# CanSat_ADCS.net
KiCad netlist of a schematic drawn in Altium Designer
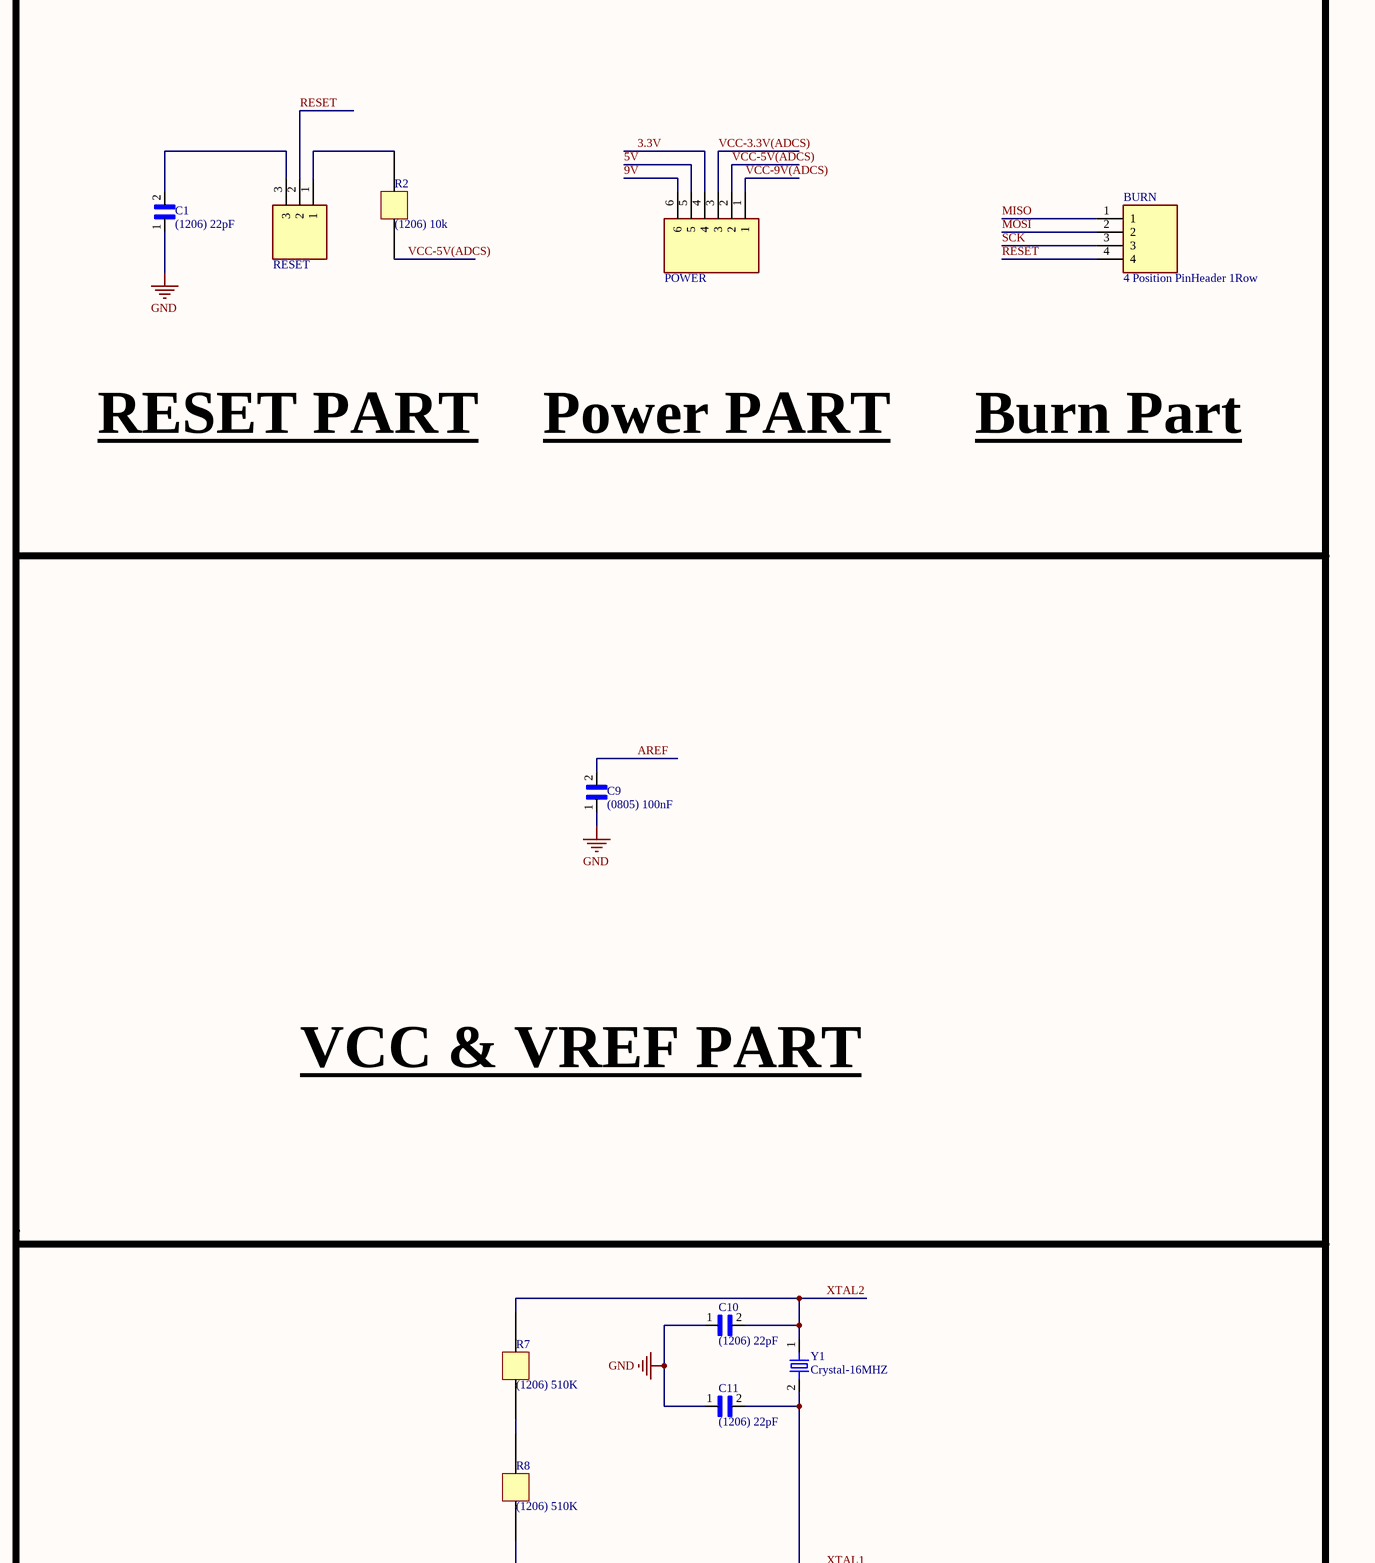
[diagram p0: CanSat ADCS.SchDoc, top left]
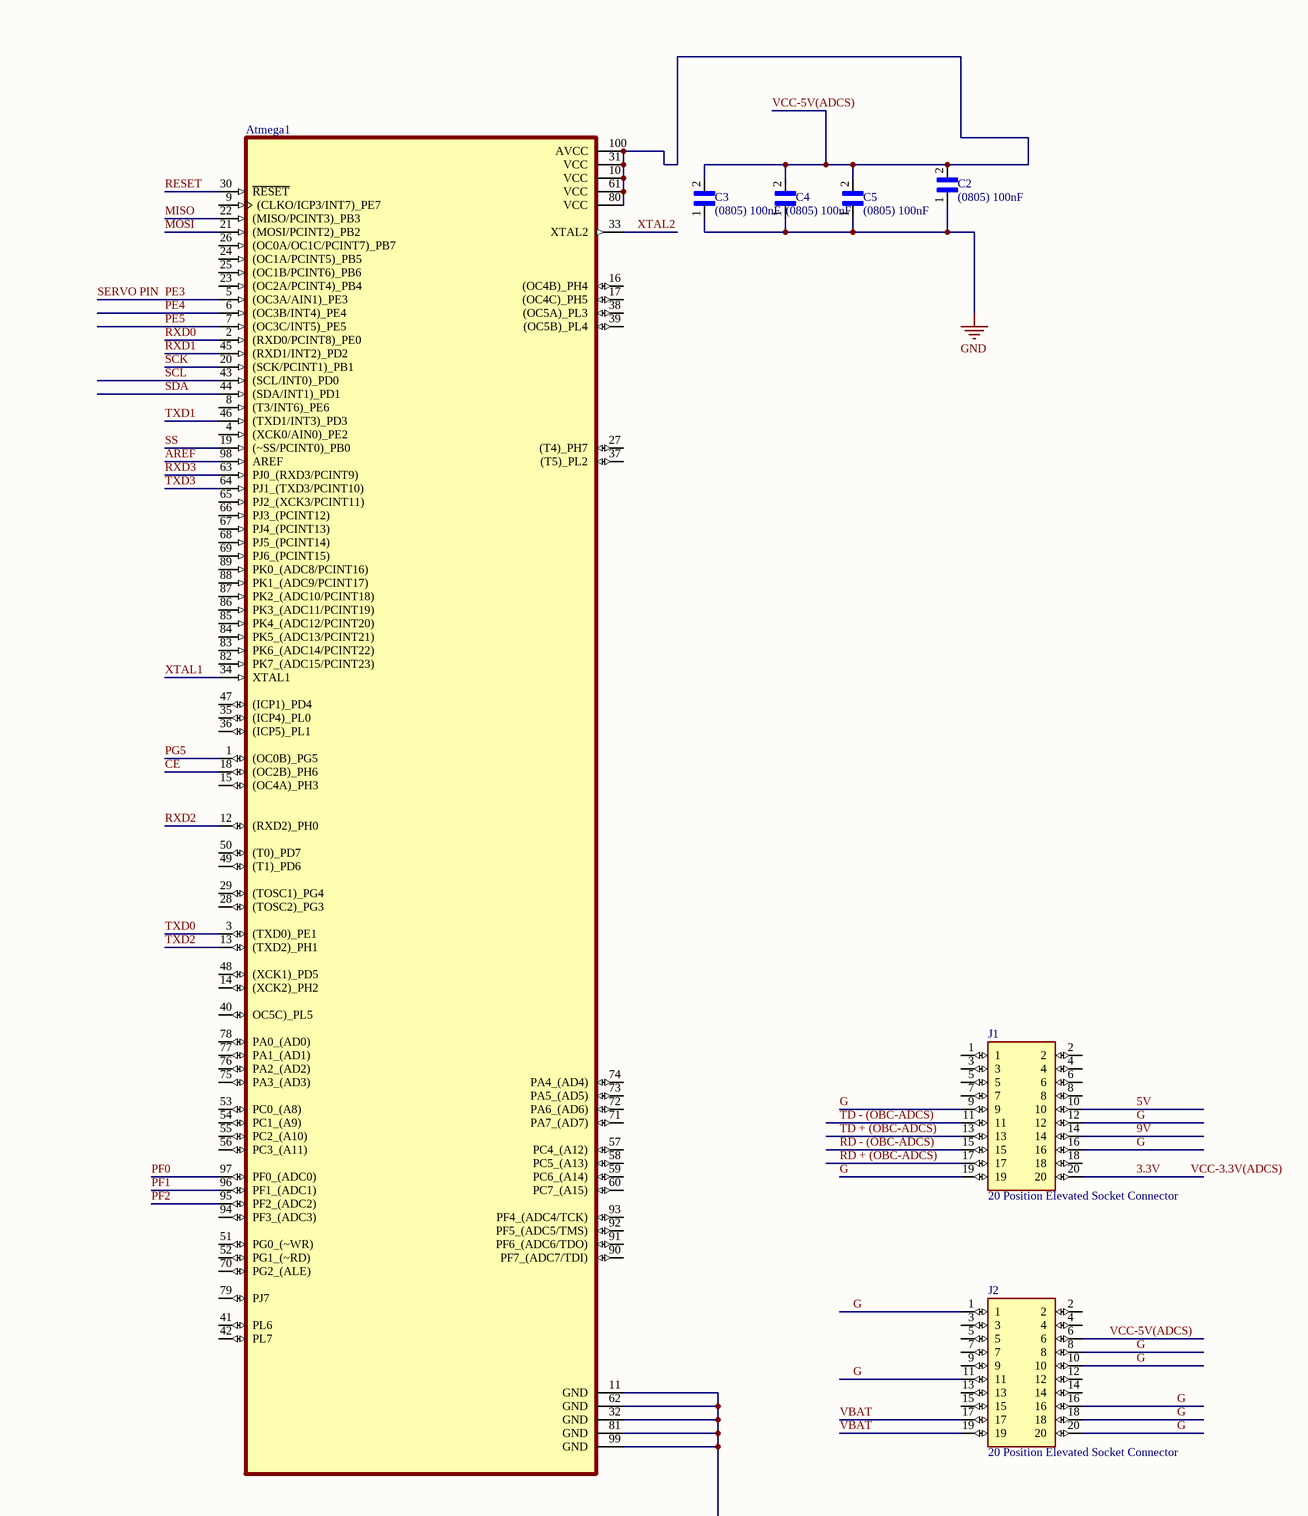
[diagram p1: CanSat ADCS.SchDoc, top middle]
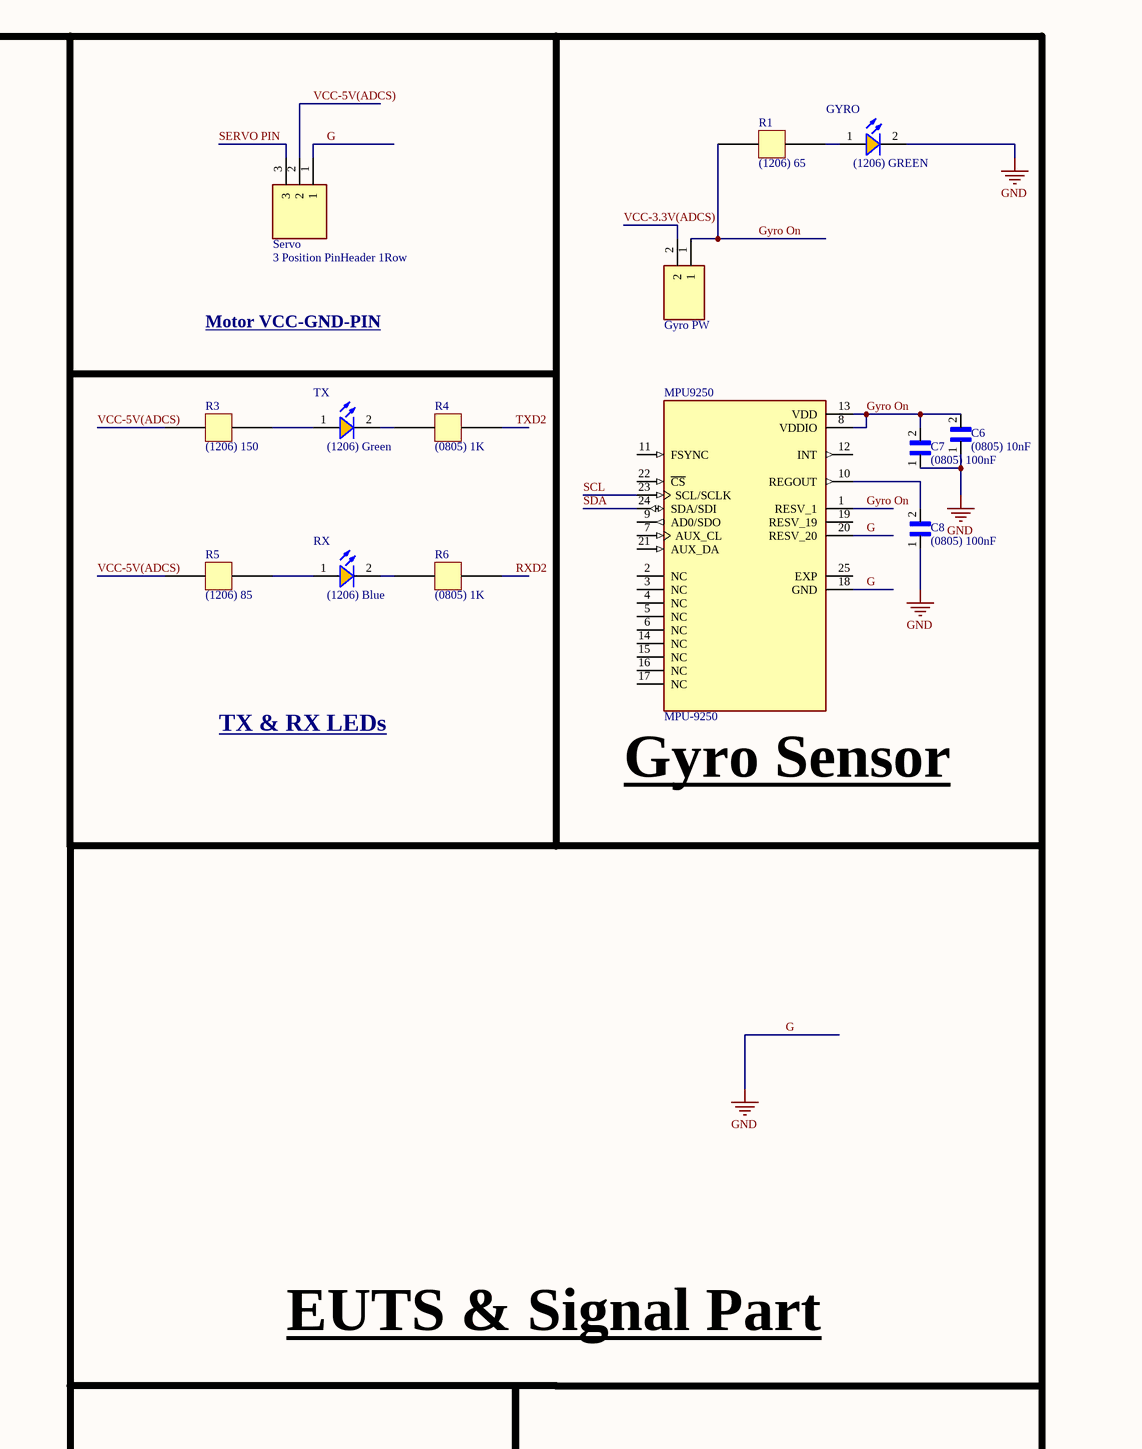
[diagram p2: CanSat ADCS.SchDoc, top right]
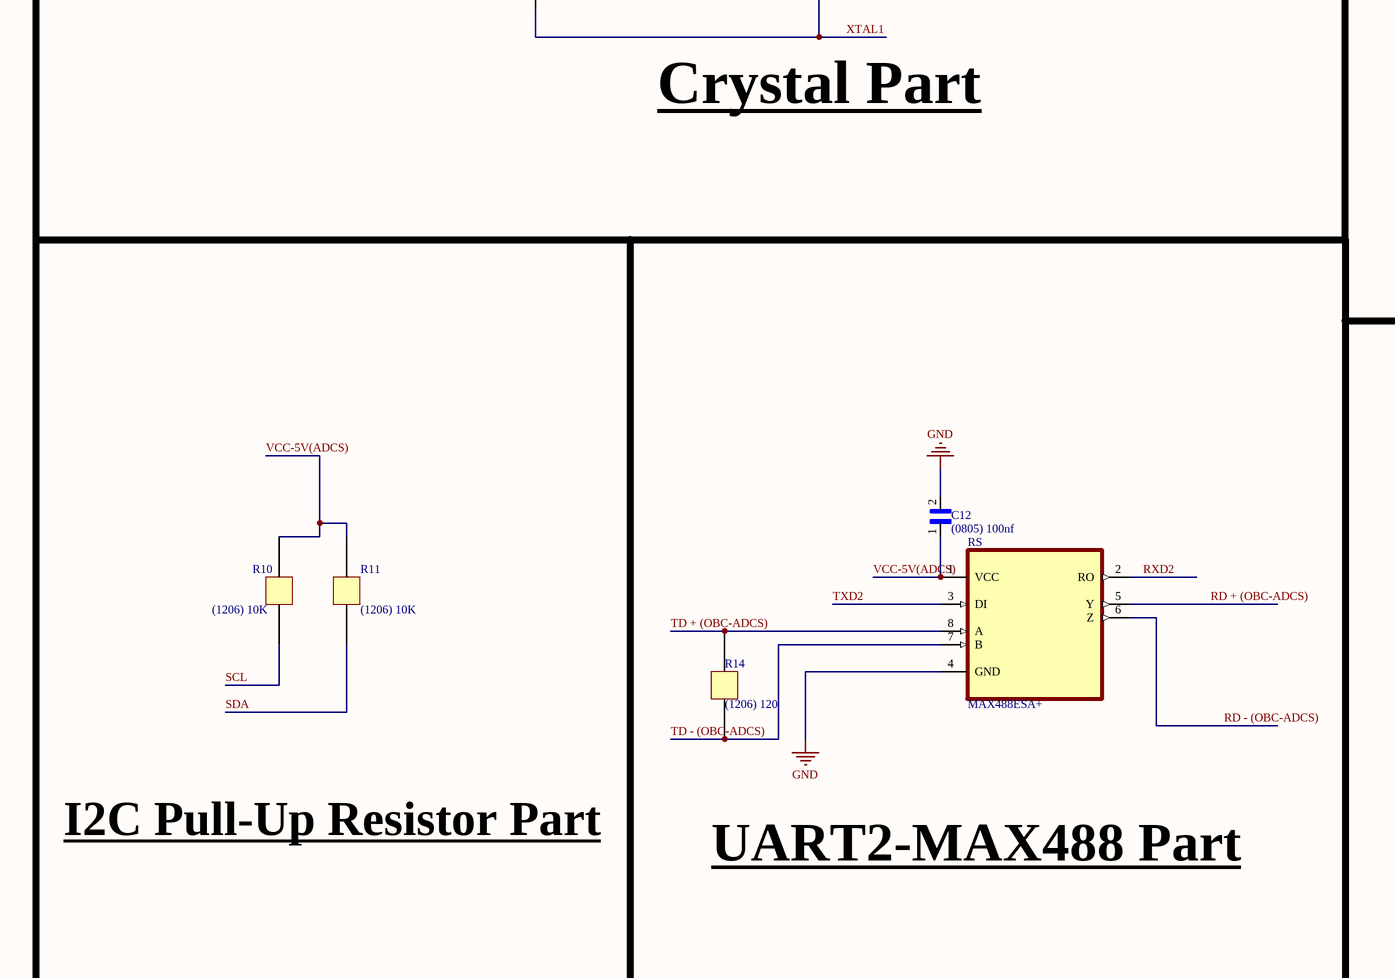
[diagram p3: CanSat ADCS.SchDoc, bottom left]
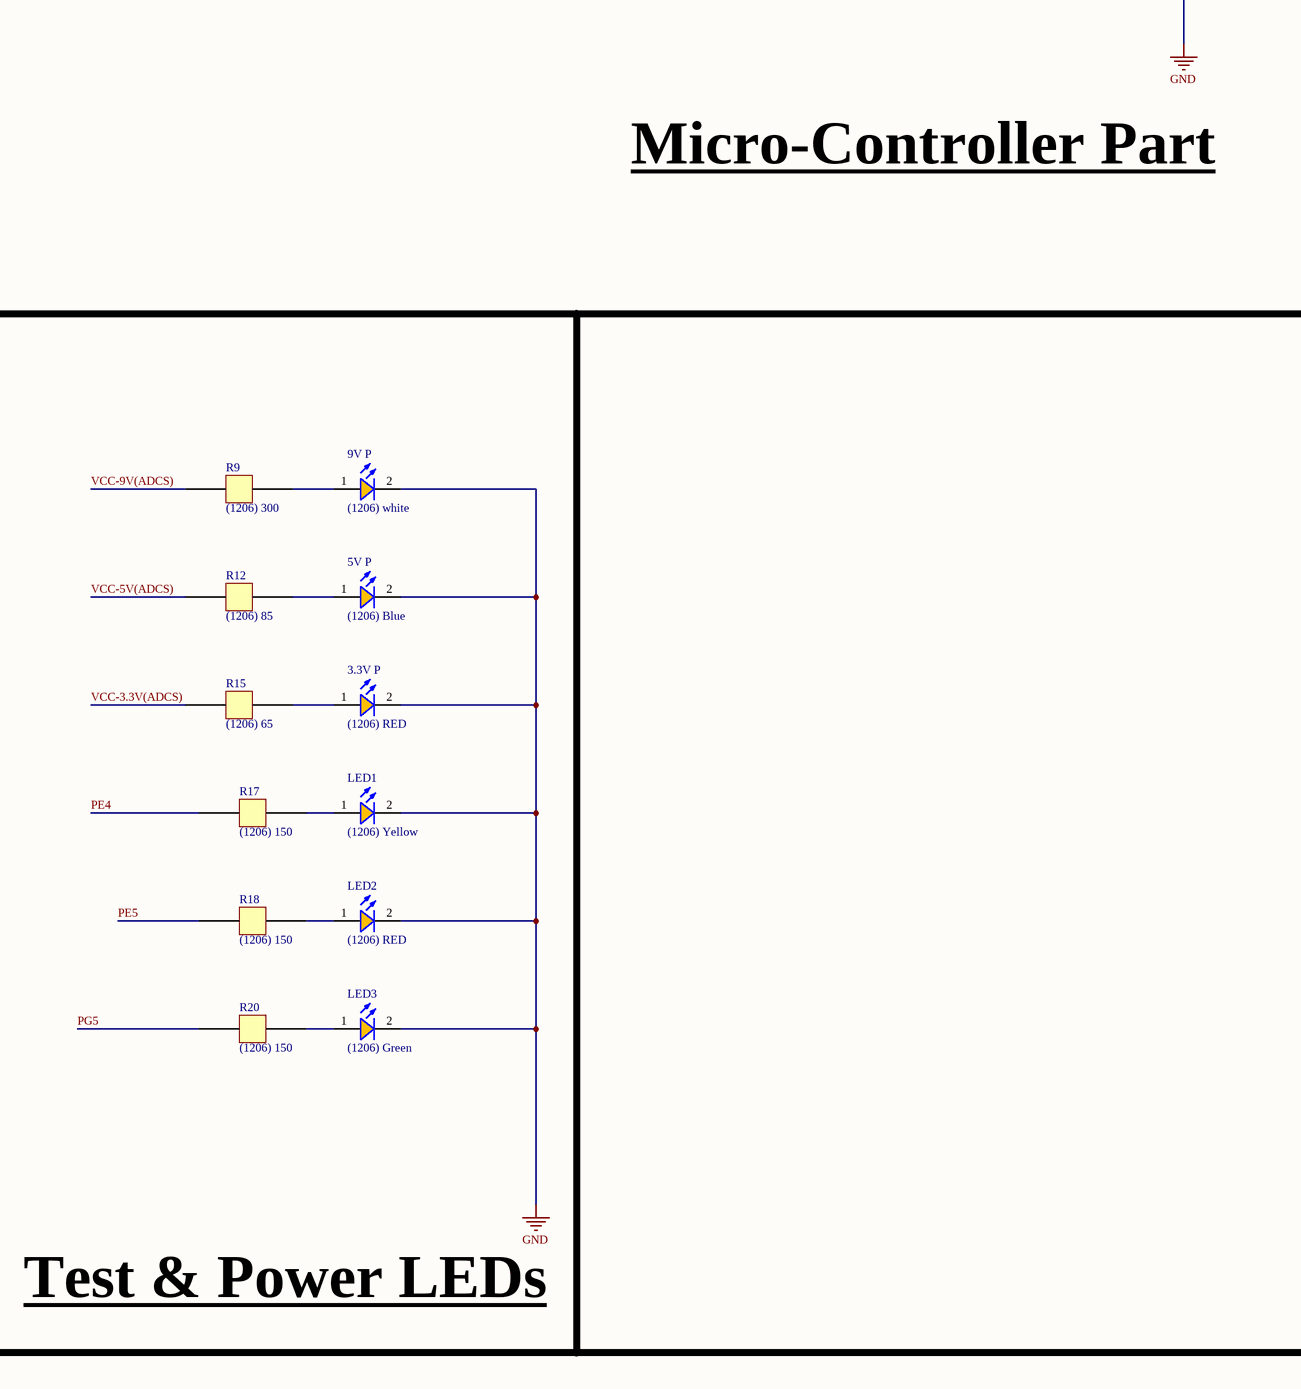
[diagram p4: CanSat ADCS.SchDoc, bottom middle]
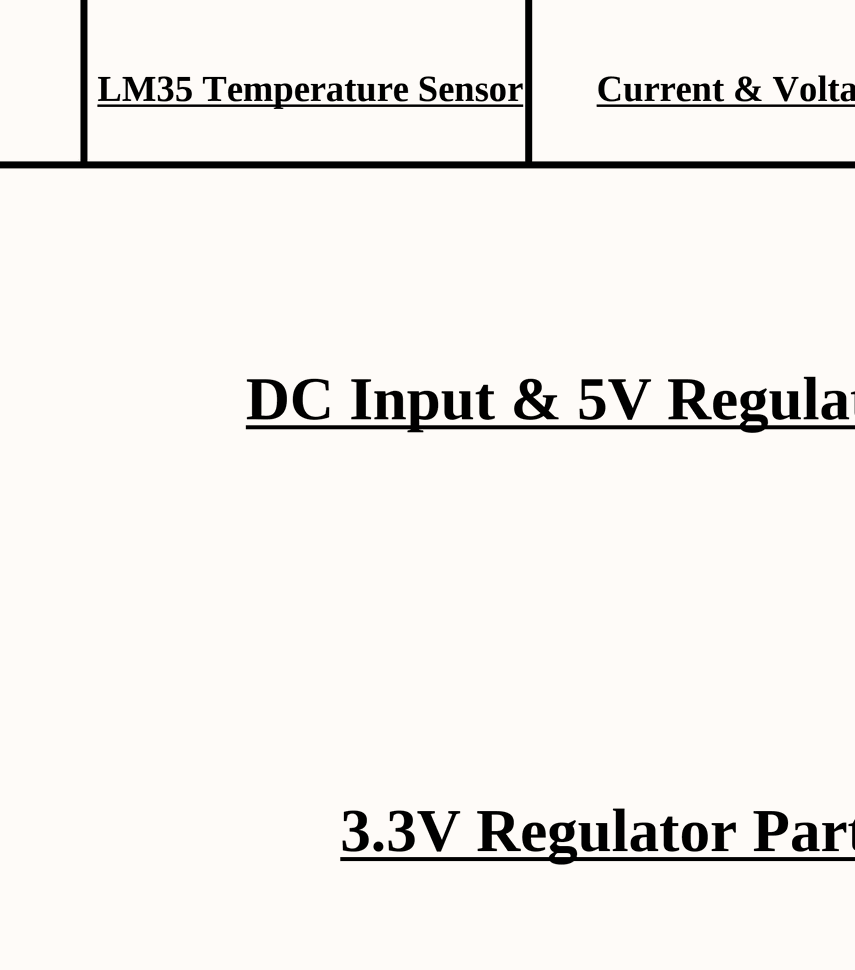
[diagram p5: CanSat ADCS.SchDoc, bottom right]

(export (version "E")
  (design (tool "Eeschema 10.0.6"))
  (components
    (comp (ref "3.3V P")
      (value "(1206) RED")
      (footprint "RESC3015X65-01")
      (description "LED SMD 1206 High Quality Forward Voltage: 3.2 V\r\nBrightness: 700 mcd")
      (fields
        (field (name "MANUFACTURER") "Wurth Elektronik")
        (field (name "MANUFACTURER PART NUMBER") "150060AS75003")
      )
      (libsource (lib "NewLib") (part "LED 1206"))
    )
    (comp (ref "5V P")
      (value "(1206) Blue")
      (footprint "RESC3015X65-01")
      (description "LED SMD 1206 High Quality Forward Voltage: 3.2 V\r\nBrightness: 700 mcd")
      (fields
        (field (name "MANUFACTURER") "Wurth Elektronik")
        (field (name "MANUFACTURER PART NUMBER") "150060AS75003")
      )
      (libsource (lib "NewLib") (part "LED 1206"))
    )
    (comp (ref "9V P")
      (value "(1206) white")
      (footprint "RESC3015X65-01")
      (description "LED SMD 1206 High Quality Forward Voltage: 3.2 V\r\nBrightness: 700 mcd")
      (fields
        (field (name "MANUFACTURER") "Wurth Elektronik")
        (field (name "MANUFACTURER PART NUMBER") "150060AS75003")
      )
      (libsource (lib "NewLib") (part "LED 1206"))
    )
    (comp (ref "Atmega1")
      (value "~")
      (footprint "QFP50P1600X1600X120-100N")
      (fields (field (name "MP") "ATMEGA2560-16AU"))
      (libsource (lib "NewLib") (part "ATMEGA2560-16AU"))
    )
    (comp (ref "BURN")
      (value "4 Position PinHeader 1Row")
      (footprint "TE_3-644456-4")
      (description "Conn Unshrouded Header HDR 4 POS 2.54mm Solder ST Thru-Hole Bag/Box")
      (fields (field (name "MP") "3-644456-4") (field (name "MF") "TE Connectivity"))
      (libsource (lib "NewLib") (part "4 Position PinHeader 1Row"))
    )
    (comp (ref "C1")
      (value "(1206) 22pF")
      (footprint "CAPC3216X125N0")
      (description "UMF316B7103KFHT/1206 Capacitor")
      (fields (field (name "MP") "UMF316B7103KFHT"))
      (libsource (lib "") (part "Capacitor 1206_1"))
    )
    (comp (ref "C2")
      (value "(0805) 100nF")
      (footprint "CAPC2012X95N-0")
      (description "UMK212SD103KD-T/CAP CER 10000PF 50V 0805")
      (fields (field (name "MP") "UMK212SD103KD-T"))
      (libsource (lib "NewLib") (part "Capacitor 0805"))
    )
    (comp (ref "C3")
      (value "(0805) 100nF")
      (footprint "CAPC2012X95N-0")
      (description "UMK212SD103KD-T/CAP CER 10000PF 50V 0805")
      (fields (field (name "MP") "UMK212SD103KD-T"))
      (libsource (lib "NewLib") (part "Capacitor 0805"))
    )
    (comp (ref "C4")
      (value "(0805) 100nF")
      (footprint "CAPC2012X95N-0")
      (description "UMK212SD103KD-T/CAP CER 10000PF 50V 0805")
      (fields (field (name "MP") "UMK212SD103KD-T"))
      (libsource (lib "NewLib") (part "Capacitor 0805"))
    )
    (comp (ref "C5")
      (value "(0805) 100nF")
      (footprint "CAPC2012X95N-0")
      (description "UMK212SD103KD-T/CAP CER 10000PF 50V 0805")
      (fields (field (name "MP") "UMK212SD103KD-T"))
      (libsource (lib "NewLib") (part "Capacitor 0805"))
    )
    (comp (ref "C6")
      (value "(0805) 10nF")
      (footprint "CAPC2012X95N-0")
      (description "UMK212SD103KD-T/CAP CER 10000PF 50V 0805")
      (fields (field (name "MP") "UMK212SD103KD-T"))
      (libsource (lib "NewLib") (part "Capacitor 0805"))
    )
    (comp (ref "C7")
      (value "(0805) 100nF")
      (footprint "CAPC2012X95N-0")
      (description "UMK212SD103KD-T/CAP CER 10000PF 50V 0805")
      (fields (field (name "MP") "UMK212SD103KD-T"))
      (libsource (lib "NewLib") (part "Capacitor 0805"))
    )
    (comp (ref "C8")
      (value "(0805) 100nF")
      (footprint "CAPC2012X95N-0")
      (description "UMK212SD103KD-T/CAP CER 10000PF 50V 0805")
      (fields (field (name "MP") "UMK212SD103KD-T"))
      (libsource (lib "NewLib") (part "Capacitor 0805"))
    )
    (comp (ref "C9")
      (value "(0805) 100nF")
      (footprint "CAPC2012X95N-0")
      (description "UMK212SD103KD-T/CAP CER 10000PF 50V 0805")
      (fields (field (name "MP") "UMK212SD103KD-T"))
      (libsource (lib "NewLib") (part "Capacitor 0805"))
    )
    (comp (ref "C10")
      (value "(1206) 22pF")
      (footprint "CAPC3216X125N0")
      (description "UMF316B7103KFHT/1206 Capacitor")
      (fields (field (name "MP") "UMF316B7103KFHT"))
      (libsource (lib "NewLib") (part "Capacitor 1206"))
    )
    (comp (ref "C11")
      (value "(1206) 22pF")
      (footprint "CAPC3216X125N0")
      (description "UMF316B7103KFHT/1206 Capacitor")
      (fields (field (name "MP") "UMF316B7103KFHT"))
      (libsource (lib "NewLib") (part "Capacitor 1206"))
    )
    (comp (ref "C12")
      (value "(0805) 100nf")
      (footprint "CAPC2012X95N-0")
      (description "UMK212SD103KD-T/CAP CER 10000PF 50V 0805")
      (fields (field (name "MP") "UMK212SD103KD-T"))
      (libsource (lib "NewLib") (part "Capacitor 0805"))
    )
    (comp (ref "GYRO")
      (value "(1206) GREEN")
      (footprint "RESC3015X65-01")
      (description "LED SMD 1206 High Quality Forward Voltage: 3.2 V\r\nBrightness: 700 mcd")
      (fields
        (field (name "MANUFACTURER") "Wurth Elektronik")
        (field (name "MANUFACTURER PART NUMBER") "150060AS75003")
      )
      (libsource (lib "NewLib") (part "LED 1206"))
    )
    (comp (ref "Gyro PW")
      (value "2 Position PinHeader")
      (footprint "TE_2-103327-2")
      (description "Cabezal del conector Agujero pasante 2 posiciones 0,100 (2,54 mm)")
      (fields (field (name "MP") "4-103327-4") (field (name "MF") "TE Connectivity"))
      (libsource (lib "NewLib") (part "2 Position PinHeader"))
    )
    (comp (ref "J1")
      (value "20 Position Elevated Socket Connector")
      (footprint "ESQ-110-XX-X-D")
      (description "20 Position Elevated Socket Connector Through Hole")
      (fields (field (name "MP") "ESQ-110-14-T-D") (field (name "MF") "Samtec"))
      (libsource (lib "NewLib") (part "20 Position Elevated Socket Connector"))
    )
    (comp (ref "J2")
      (value "20 Position Elevated Socket Connector")
      (footprint "ESQ-110-XX-X-D")
      (description "20 Position Elevated Socket Connector Through Hole")
      (fields (field (name "MP") "ESQ-110-14-T-D") (field (name "MF") "Samtec"))
      (libsource (lib "NewLib") (part "20 Position Elevated Socket Connector"))
    )
    (comp (ref "LED1")
      (value "(1206) Yellow")
      (footprint "RESC3015X65-01")
      (description "LED SMD 1206 High Quality Forward Voltage: 3.2 V\r\nBrightness: 700 mcd")
      (fields
        (field (name "MANUFACTURER") "Wurth Elektronik")
        (field (name "MANUFACTURER PART NUMBER") "150060AS75003")
      )
      (libsource (lib "NewLib") (part "LED 1206"))
    )
    (comp (ref "LED2")
      (value "(1206) RED")
      (footprint "RESC3015X65-01")
      (description "LED SMD 1206 High Quality Forward Voltage: 3.2 V\r\nBrightness: 700 mcd")
      (fields
        (field (name "MANUFACTURER") "Wurth Elektronik")
        (field (name "MANUFACTURER PART NUMBER") "150060AS75003")
      )
      (libsource (lib "NewLib") (part "LED 1206"))
    )
    (comp (ref "LED3")
      (value "(1206) Green")
      (footprint "RESC3015X65-01")
      (description "LED SMD 1206 High Quality Forward Voltage: 3.2 V\r\nBrightness: 700 mcd")
      (fields
        (field (name "MANUFACTURER") "Wurth Elektronik")
        (field (name "MANUFACTURER PART NUMBER") "150060AS75003")
      )
      (libsource (lib "NewLib") (part "LED 1206"))
    )
    (comp (ref "MPU9250")
      (value "MPU-9250")
      (footprint "QFN40P300X300X105-25N")
      (fields (field (name "MF") "TDK InvenSense"))
      (libsource (lib "NewLib") (part "MPU-9250"))
    )
    (comp (ref "POWER")
      (value "6 Position PinHeader 1Row")
      (footprint "TE_6-146285-6")
      (description "Connector Header Through Hole 6 position 0.100 (2.54mm)")
      (fields (field (name "MP") "5-146285-6") (field (name "DIGI-KEY_PART_NUMBER") "A122872-ND"))
      (libsource (lib "NewLib") (part "6 Position PinHeader 1Row"))
    )
    (comp (ref "R1")
      (value "(1206) 65")
      (footprint "CAPC3216X125N0")
      (libsource (lib "") (part "Resistor 1206_1"))
    )
    (comp (ref "R2")
      (value "(1206) 10k")
      (footprint "CAPC3216X125N0")
      (libsource (lib "") (part "Resistor 1206_2"))
    )
    (comp (ref "R3")
      (value "(1206) 150")
      (footprint "CAPC3216X125N0")
      (libsource (lib "") (part "Resistor 1206_1"))
    )
    (comp (ref "R4")
      (value "(0805) 1K")
      (footprint "CAPC2012X95N-0")
      (libsource (lib "NewLib") (part "Resistor 0805"))
    )
    (comp (ref "R5")
      (value "(1206) 85")
      (footprint "CAPC3216X125N0")
      (libsource (lib "") (part "Resistor 1206_1"))
    )
    (comp (ref "R6")
      (value "(0805) 1K")
      (footprint "CAPC2012X95N-0")
      (libsource (lib "NewLib") (part "Resistor 0805"))
    )
    (comp (ref "R7")
      (value "(1206) 510K")
      (footprint "CAPC3216X125N0")
      (libsource (lib "") (part "Resistor 1206_2"))
    )
    (comp (ref "R8")
      (value "(1206) 510K")
      (footprint "CAPC3216X125N0")
      (libsource (lib "") (part "Resistor 1206_2"))
    )
    (comp (ref "R9")
      (value "(1206) 300")
      (footprint "CAPC3216X125N0")
      (libsource (lib "") (part "Resistor 1206_1"))
    )
    (comp (ref "R10")
      (value "(1206) 10K")
      (footprint "CAPC3216X125N0")
      (libsource (lib "NewLib") (part "Resistor 1206"))
    )
    (comp (ref "R11")
      (value "(1206) 10K")
      (footprint "CAPC3216X125N0")
      (libsource (lib "NewLib") (part "Resistor 1206"))
    )
    (comp (ref "R12")
      (value "(1206) 85")
      (footprint "CAPC3216X125N0")
      (libsource (lib "") (part "Resistor 1206_1"))
    )
    (comp (ref "R14")
      (value "(1206) 120")
      (footprint "CAPC3216X125N0")
      (libsource (lib "") (part "Resistor 1206_2"))
    )
    (comp (ref "R15")
      (value "(1206) 65")
      (footprint "CAPC3216X125N0")
      (libsource (lib "") (part "Resistor 1206_1"))
    )
    (comp (ref "R17")
      (value "(1206) 150")
      (footprint "CAPC3216X125N0")
      (libsource (lib "") (part "Resistor 1206_1"))
    )
    (comp (ref "R18")
      (value "(1206) 150")
      (footprint "CAPC3216X125N0")
      (libsource (lib "") (part "Resistor 1206_1"))
    )
    (comp (ref "R20")
      (value "(1206) 150")
      (footprint "CAPC3216X125N0")
      (libsource (lib "") (part "Resistor 1206_1"))
    )
    (comp (ref "RESET")
      (value "3 Position PinHeader 1Row")
      (footprint "TE_3-103327-3")
      (description "Conn Unshrouded Header HDR 3 POS 2.54mm Solder ST Thru-Hole Carton")
      (fields (field (name "MF") "TE Connectivity") (field (name "MP") "4-103327-5"))
      (libsource (lib "NewLib") (part "3 Position PinHeader 1Row"))
    )
    (comp (ref "RS")
      (value "MAX488ESA+")
      (footprint "SOIC127P600X175-8N0")
      (description "1/1 Transceiver Full RS422, RS485 8-SOIC")
      (fields (field (name "MP") "MAX488ESA+T") (field (name "MF") "Maxim Integrated"))
      (libsource (lib "NewLib") (part "MAX488ESA+"))
    )
    (comp (ref "RX")
      (value "(1206) Blue")
      (footprint "RESC3015X65-01")
      (description "LED SMD 1206 High Quality Forward Voltage: 3.2 V\r\nBrightness: 700 mcd")
      (fields
        (field (name "MANUFACTURER") "Wurth Elektronik")
        (field (name "MANUFACTURER PART NUMBER") "150060AS75003")
      )
      (libsource (lib "NewLib") (part "LED 1206"))
    )
    (comp (ref "Servo")
      (value "3 Position PinHeader 1Row")
      (footprint "TE_3-103327-3")
      (description "Conn Unshrouded Header HDR 3 POS 2.54mm Solder ST Thru-Hole Carton")
      (fields (field (name "MF") "TE Connectivity") (field (name "MP") "4-103327-5"))
      (libsource (lib "NewLib") (part "3 Position PinHeader 1Row"))
    )
    (comp (ref "TX")
      (value "(1206) Green")
      (footprint "RESC3015X65-01")
      (description "LED SMD 1206 High Quality Forward Voltage: 3.2 V\r\nBrightness: 700 mcd")
      (fields
        (field (name "MANUFACTURER") "Wurth Elektronik")
        (field (name "MANUFACTURER PART NUMBER") "150060AS75003")
      )
      (libsource (lib "NewLib") (part "LED 1206"))
    )
    (comp (ref "Y1")
      (value "Crystal-16MHZ")
      (footprint "XTAL1140X490X430N-0")
      (libsource (lib "NewLib") (part "Crystal-16MHZ"))
    )
  )
  (nets
    (net (code "1") (name "/3.3V") (class "Default")
      (node (ref "Gyro PW") (pin "2") (pinfunction "2_2") (pintype "passive"))
      (node (ref "J1") (pin "20") (pinfunction "20_20") (pintype "bidirectional"))
      (node (ref "POWER") (pin "3") (pinfunction "3_3") (pintype "passive"))
      (node (ref "POWER") (pin "4") (pinfunction "4_4") (pintype "passive"))
      (node (ref "R15") (pin "1") (pinfunction "1_1") (pintype "passive"))
    )
    (net (code "2") (name "/5V") (class "Default")
      (node (ref "J1") (pin "10") (pinfunction "10_10") (pintype "bidirectional"))
      (node (ref "POWER") (pin "5") (pinfunction "5_5") (pintype "passive"))
    )
    (net (code "3") (name "/9V") (class "Default")
      (node (ref "J1") (pin "14") (pinfunction "14_14") (pintype "bidirectional"))
      (node (ref "POWER") (pin "6") (pinfunction "6_6") (pintype "passive"))
    )
    (net (code "4") (name "/AREF") (class "Default")
      (node (ref "Atmega1") (pin "98") (pinfunction "AREF_98") (pintype "input"))
      (node (ref "C9") (pin "2") (pinfunction "2_2") (pintype "passive"))
    )
    (net (code "5") (name "/CE") (class "Default")
      (node (ref "Atmega1") (pin "18") (pinfunction "(OC2B)_PH6_18") (pintype "bidirectional"))
    )
    (net (code "6") (name "/Gyro On") (class "Default")
      (node (ref "C6") (pin "2") (pinfunction "2_2") (pintype "passive"))
      (node (ref "C7") (pin "2") (pinfunction "2_2") (pintype "passive"))
      (node (ref "Gyro PW") (pin "1") (pinfunction "1_1") (pintype "passive"))
      (node (ref "MPU9250") (pin "1") (pinfunction "RESV_1_1") (pintype "power_in"))
      (node (ref "MPU9250") (pin "13") (pinfunction "VDD_13") (pintype "power_in"))
      (node (ref "MPU9250") (pin "8") (pinfunction "VDDIO_8") (pintype "power_in"))
      (node (ref "R1") (pin "1") (pinfunction "1_1") (pintype "passive"))
    )
    (net (code "7") (name "/MISO") (class "Default")
      (node (ref "Atmega1") (pin "22") (pinfunction "(MISO/PCINT3)_PB3_22") (pintype "input"))
      (node (ref "BURN") (pin "1") (pinfunction "1_1") (pintype "passive"))
    )
    (net (code "8") (name "/MOSI") (class "Default")
      (node (ref "Atmega1") (pin "21") (pinfunction "(MOSI/PCINT2)_PB2_21") (pintype "input"))
      (node (ref "BURN") (pin "2") (pinfunction "2_2") (pintype "passive"))
    )
    (net (code "9") (name "/PE3") (class "Default")
      (node (ref "Atmega1") (pin "5") (pinfunction "(OC3A/AIN1)_PE3_5") (pintype "input"))
      (node (ref "Servo") (pin "3") (pinfunction "3_3") (pintype "passive"))
    )
    (net (code "10") (name "/PE4") (class "Default")
      (node (ref "Atmega1") (pin "6") (pinfunction "(OC3B/INT4)_PE4_6") (pintype "input"))
      (node (ref "R17") (pin "1") (pinfunction "1_1") (pintype "passive"))
    )
    (net (code "11") (name "/PE5") (class "Default")
      (node (ref "Atmega1") (pin "7") (pinfunction "(OC3C/INT5)_PE5_7") (pintype "input"))
      (node (ref "R18") (pin "1") (pinfunction "1_1") (pintype "passive"))
    )
    (net (code "12") (name "/PF0") (class "Default")
      (node (ref "Atmega1") (pin "97") (pinfunction "PF0_(ADC0)_97") (pintype "bidirectional"))
    )
    (net (code "13") (name "/PF1") (class "Default")
      (node (ref "Atmega1") (pin "96") (pinfunction "PF1_(ADC1)_96") (pintype "bidirectional"))
    )
    (net (code "14") (name "/PF2") (class "Default")
      (node (ref "Atmega1") (pin "95") (pinfunction "PF2_(ADC2)_95") (pintype "bidirectional"))
    )
    (net (code "15") (name "/PG5") (class "Default")
      (node (ref "Atmega1") (pin "1") (pinfunction "(OC0B)_PG5_1") (pintype "bidirectional"))
      (node (ref "R20") (pin "1") (pinfunction "1_1") (pintype "passive"))
    )
    (net (code "16") (name "/RD + (OBC-ADCS)") (class "Default")
      (node (ref "J1") (pin "17") (pinfunction "17_17") (pintype "bidirectional"))
      (node (ref "RS") (pin "5") (pinfunction "Y_5") (pintype "output"))
    )
    (net (code "17") (name "/RD - (OBC-ADCS)") (class "Default")
      (node (ref "J1") (pin "15") (pinfunction "15_15") (pintype "bidirectional"))
      (node (ref "RS") (pin "6") (pinfunction "Z_6") (pintype "output"))
    )
    (net (code "18") (name "/RESET") (class "Default")
      (node (ref "Atmega1") (pin "30") (pinfunction "~{RESET}_30") (pintype "input"))
      (node (ref "BURN") (pin "4") (pinfunction "4_4") (pintype "passive"))
      (node (ref "RESET") (pin "2") (pinfunction "2_2") (pintype "passive"))
    )
    (net (code "19") (name "/RXD0") (class "Default")
      (node (ref "Atmega1") (pin "2") (pinfunction "(RXD0/PCINT8)_PE0_2") (pintype "input"))
    )
    (net (code "20") (name "/RXD1") (class "Default")
      (node (ref "Atmega1") (pin "45") (pinfunction "(RXD1/INT2)_PD2_45") (pintype "input"))
    )
    (net (code "21") (name "/RXD2") (class "Default")
      (node (ref "Atmega1") (pin "12") (pinfunction "(RXD2)_PH0_12") (pintype "bidirectional"))
      (node (ref "R6") (pin "2") (pinfunction "2_2") (pintype "passive"))
      (node (ref "RS") (pin "2") (pinfunction "RO_2") (pintype "output"))
    )
    (net (code "22") (name "/RXD3") (class "Default")
      (node (ref "Atmega1") (pin "63") (pinfunction "PJ0_(RXD3/PCINT9)_63") (pintype "input"))
    )
    (net (code "23") (name "/SCK") (class "Default")
      (node (ref "Atmega1") (pin "20") (pinfunction "(SCK/PCINT1)_PB1_20") (pintype "input"))
      (node (ref "BURN") (pin "3") (pinfunction "3_3") (pintype "passive"))
    )
    (net (code "24") (name "/SCL") (class "Default")
      (node (ref "Atmega1") (pin "43") (pinfunction "(SCL/INT0)_PD0_43") (pintype "input"))
      (node (ref "MPU9250") (pin "23") (pinfunction "SCL/SCLK_23") (pintype "input"))
      (node (ref "R10") (pin "2") (pinfunction "2_2") (pintype "passive"))
    )
    (net (code "25") (name "/SDA") (class "Default")
      (node (ref "Atmega1") (pin "44") (pinfunction "(SDA/INT1)_PD1_44") (pintype "input"))
      (node (ref "MPU9250") (pin "24") (pinfunction "SDA/SDI_24") (pintype "bidirectional"))
      (node (ref "R11") (pin "2") (pinfunction "2_2") (pintype "passive"))
    )
    (net (code "26") (name "/SS") (class "Default")
      (node (ref "Atmega1") (pin "19") (pinfunction "(~SS/PCINT0)_PB0_19") (pintype "input"))
    )
    (net (code "27") (name "/TD + (OBC-ADCS)") (class "Default")
      (node (ref "J1") (pin "13") (pinfunction "13_13") (pintype "bidirectional"))
      (node (ref "R14") (pin "2") (pinfunction "2_2") (pintype "passive"))
      (node (ref "RS") (pin "8") (pinfunction "A_8") (pintype "input"))
    )
    (net (code "28") (name "/TD - (OBC-ADCS)") (class "Default")
      (node (ref "J1") (pin "11") (pinfunction "11_11") (pintype "bidirectional"))
      (node (ref "R14") (pin "1") (pinfunction "1_1") (pintype "passive"))
      (node (ref "RS") (pin "7") (pinfunction "B_7") (pintype "input"))
    )
    (net (code "29") (name "/TXD0") (class "Default")
      (node (ref "Atmega1") (pin "3") (pinfunction "(TXD0)_PE1_3") (pintype "bidirectional"))
    )
    (net (code "30") (name "/TXD1") (class "Default")
      (node (ref "Atmega1") (pin "46") (pinfunction "(TXD1/INT3)_PD3_46") (pintype "input"))
    )
    (net (code "31") (name "/TXD2") (class "Default")
      (node (ref "Atmega1") (pin "13") (pinfunction "(TXD2)_PH1_13") (pintype "bidirectional"))
      (node (ref "R4") (pin "2") (pinfunction "2_2") (pintype "passive"))
      (node (ref "RS") (pin "3") (pinfunction "DI_3") (pintype "input"))
    )
    (net (code "32") (name "/TXD3") (class "Default")
      (node (ref "Atmega1") (pin "64") (pinfunction "PJ1_(TXD3/PCINT10)_64") (pintype "input"))
    )
    (net (code "33") (name "/VBAT") (class "Default")
      (node (ref "J2") (pin "17") (pinfunction "17_17") (pintype "bidirectional"))
      (node (ref "J2") (pin "19") (pinfunction "19_19") (pintype "bidirectional"))
    )
    (net (code "34") (name "/VCC-5V(ADCS)") (class "Default")
      (node (ref "Atmega1") (pin "10") (pinfunction "VCC_10") (pintype "power_in"))
      (node (ref "Atmega1") (pin "100") (pinfunction "AVCC_100") (pintype "power_in"))
      (node (ref "Atmega1") (pin "31") (pinfunction "VCC_31") (pintype "power_in"))
      (node (ref "Atmega1") (pin "61") (pinfunction "VCC_61") (pintype "power_in"))
      (node (ref "Atmega1") (pin "80") (pinfunction "VCC_80") (pintype "power_in"))
      (node (ref "C12") (pin "1") (pinfunction "1_1") (pintype "passive"))
      (node (ref "C2") (pin "2") (pinfunction "2_2") (pintype "passive"))
      (node (ref "C3") (pin "2") (pinfunction "2_2") (pintype "passive"))
      (node (ref "C4") (pin "2") (pinfunction "2_2") (pintype "passive"))
      (node (ref "C5") (pin "2") (pinfunction "2_2") (pintype "passive"))
      (node (ref "J2") (pin "6") (pinfunction "6_6") (pintype "bidirectional"))
      (node (ref "POWER") (pin "2") (pinfunction "2_2") (pintype "passive"))
      (node (ref "R10") (pin "1") (pinfunction "1_1") (pintype "passive"))
      (node (ref "R11") (pin "1") (pinfunction "1_1") (pintype "passive"))
      (node (ref "R12") (pin "1") (pinfunction "1_1") (pintype "passive"))
      (node (ref "R2") (pin "1") (pinfunction "1_1") (pintype "passive"))
      (node (ref "R3") (pin "1") (pinfunction "1_1") (pintype "passive"))
      (node (ref "R5") (pin "1") (pinfunction "1_1") (pintype "passive"))
      (node (ref "RS") (pin "1") (pinfunction "VCC_1") (pintype "power_in"))
      (node (ref "Servo") (pin "2") (pinfunction "2_2") (pintype "passive"))
    )
    (net (code "35") (name "/VCC-9V(ADCS)") (class "Default")
      (node (ref "POWER") (pin "1") (pinfunction "1_1") (pintype "passive"))
      (node (ref "R9") (pin "1") (pinfunction "1_1") (pintype "passive"))
    )
    (net (code "36") (name "/XTAL1") (class "Default")
      (node (ref "Atmega1") (pin "34") (pinfunction "XTAL1_34") (pintype "input"))
      (node (ref "C11") (pin "2") (pinfunction "2_2") (pintype "passive"))
      (node (ref "R8") (pin "1") (pinfunction "1_1") (pintype "passive"))
      (node (ref "Y1") (pin "2") (pinfunction "2_2") (pintype "passive"))
    )
    (net (code "37") (name "/XTAL2") (class "Default")
      (node (ref "Atmega1") (pin "33") (pinfunction "XTAL2_33") (pintype "output"))
      (node (ref "C10") (pin "2") (pinfunction "2_2") (pintype "passive"))
      (node (ref "R7") (pin "2") (pinfunction "2_2") (pintype "passive"))
      (node (ref "Y1") (pin "1") (pinfunction "1_1") (pintype "passive"))
    )
    (net (code "38") (name "GND") (class "Default")
      (node (ref "3.3V P") (pin "2") (pinfunction "K_2") (pintype "passive"))
      (node (ref "5V P") (pin "2") (pinfunction "K_2") (pintype "passive"))
      (node (ref "9V P") (pin "2") (pinfunction "K_2") (pintype "passive"))
      (node (ref "Atmega1") (pin "11") (pinfunction "GND_11") (pintype "power_in"))
      (node (ref "Atmega1") (pin "32") (pinfunction "GND_32") (pintype "power_in"))
      (node (ref "Atmega1") (pin "62") (pinfunction "GND_62") (pintype "power_in"))
      (node (ref "Atmega1") (pin "81") (pinfunction "GND_81") (pintype "power_in"))
      (node (ref "Atmega1") (pin "99") (pinfunction "GND_99") (pintype "power_in"))
      (node (ref "C1") (pin "1") (pinfunction "1_1") (pintype "passive"))
      (node (ref "C10") (pin "1") (pinfunction "1_1") (pintype "passive"))
      (node (ref "C11") (pin "1") (pinfunction "1_1") (pintype "passive"))
      (node (ref "C12") (pin "2") (pinfunction "2_2") (pintype "passive"))
      (node (ref "C2") (pin "1") (pinfunction "1_1") (pintype "passive"))
      (node (ref "C3") (pin "1") (pinfunction "1_1") (pintype "passive"))
      (node (ref "C4") (pin "1") (pinfunction "1_1") (pintype "passive"))
      (node (ref "C5") (pin "1") (pinfunction "1_1") (pintype "passive"))
      (node (ref "C6") (pin "1") (pinfunction "1_1") (pintype "passive"))
      (node (ref "C7") (pin "1") (pinfunction "1_1") (pintype "passive"))
      (node (ref "C8") (pin "1") (pinfunction "1_1") (pintype "passive"))
      (node (ref "C9") (pin "1") (pinfunction "1_1") (pintype "passive"))
      (node (ref "GYRO") (pin "2") (pinfunction "K_2") (pintype "passive"))
      (node (ref "J1") (pin "12") (pinfunction "12_12") (pintype "bidirectional"))
      (node (ref "J1") (pin "16") (pinfunction "16_16") (pintype "bidirectional"))
      (node (ref "J1") (pin "19") (pinfunction "19_19") (pintype "bidirectional"))
      (node (ref "J1") (pin "9") (pinfunction "9_9") (pintype "bidirectional"))
      (node (ref "J2") (pin "1") (pinfunction "1_1") (pintype "bidirectional"))
      (node (ref "J2") (pin "10") (pinfunction "10_10") (pintype "bidirectional"))
      (node (ref "J2") (pin "11") (pinfunction "11_11") (pintype "bidirectional"))
      (node (ref "J2") (pin "16") (pinfunction "16_16") (pintype "bidirectional"))
      (node (ref "J2") (pin "18") (pinfunction "18_18") (pintype "bidirectional"))
      (node (ref "J2") (pin "20") (pinfunction "20_20") (pintype "bidirectional"))
      (node (ref "J2") (pin "8") (pinfunction "8_8") (pintype "bidirectional"))
      (node (ref "LED1") (pin "2") (pinfunction "K_2") (pintype "passive"))
      (node (ref "LED2") (pin "2") (pinfunction "K_2") (pintype "passive"))
      (node (ref "LED3") (pin "2") (pinfunction "K_2") (pintype "passive"))
      (node (ref "MPU9250") (pin "18") (pinfunction "GND_18") (pintype "power_in"))
      (node (ref "MPU9250") (pin "20") (pinfunction "RESV_20_20") (pintype "power_in"))
      (node (ref "RS") (pin "4") (pinfunction "GND_4") (pintype "passive"))
      (node (ref "Servo") (pin "1") (pinfunction "1_1") (pintype "passive"))
    )
    (net (code "39") (name "Net-(3.3V P-A)") (class "Default")
      (node (ref "3.3V P") (pin "1") (pinfunction "A_1") (pintype "passive"))
      (node (ref "R15") (pin "2") (pinfunction "2_2") (pintype "passive"))
    )
    (net (code "40") (name "Net-(5V P-A)") (class "Default")
      (node (ref "5V P") (pin "1") (pinfunction "A_1") (pintype "passive"))
      (node (ref "R12") (pin "2") (pinfunction "2_2") (pintype "passive"))
    )
    (net (code "41") (name "Net-(9V P-A)") (class "Default")
      (node (ref "9V P") (pin "1") (pinfunction "A_1") (pintype "passive"))
      (node (ref "R9") (pin "2") (pinfunction "2_2") (pintype "passive"))
    )
    (net (code "42") (name "Net-(C1-Pad2)") (class "Default")
      (node (ref "C1") (pin "2") (pinfunction "2_2") (pintype "passive"))
      (node (ref "RESET") (pin "3") (pinfunction "3_3") (pintype "passive"))
    )
    (net (code "43") (name "Net-(GYRO-A)") (class "Default")
      (node (ref "GYRO") (pin "1") (pinfunction "A_1") (pintype "passive"))
      (node (ref "R1") (pin "2") (pinfunction "2_2") (pintype "passive"))
    )
    (net (code "44") (name "Net-(LED1-A)") (class "Default")
      (node (ref "LED1") (pin "1") (pinfunction "A_1") (pintype "passive"))
      (node (ref "R17") (pin "2") (pinfunction "2_2") (pintype "passive"))
    )
    (net (code "45") (name "Net-(LED2-A)") (class "Default")
      (node (ref "LED2") (pin "1") (pinfunction "A_1") (pintype "passive"))
      (node (ref "R18") (pin "2") (pinfunction "2_2") (pintype "passive"))
    )
    (net (code "46") (name "Net-(LED3-A)") (class "Default")
      (node (ref "LED3") (pin "1") (pinfunction "A_1") (pintype "passive"))
      (node (ref "R20") (pin "2") (pinfunction "2_2") (pintype "passive"))
    )
    (net (code "47") (name "Net-(MPU9250-REGOUT)") (class "Default")
      (node (ref "C8") (pin "2") (pinfunction "2_2") (pintype "passive"))
      (node (ref "MPU9250") (pin "10") (pinfunction "REGOUT_10") (pintype "output"))
    )
    (net (code "48") (name "Net-(R2-Pad2)") (class "Default")
      (node (ref "R2") (pin "2") (pinfunction "2_2") (pintype "passive"))
      (node (ref "RESET") (pin "1") (pinfunction "1_1") (pintype "passive"))
    )
    (net (code "49") (name "Net-(R7-Pad1)") (class "Default")
      (node (ref "R7") (pin "1") (pinfunction "1_1") (pintype "passive"))
      (node (ref "R8") (pin "2") (pinfunction "2_2") (pintype "passive"))
    )
    (net (code "50") (name "Net-(RX-A)") (class "Default")
      (node (ref "R5") (pin "2") (pinfunction "2_2") (pintype "passive"))
      (node (ref "RX") (pin "1") (pinfunction "A_1") (pintype "passive"))
    )
    (net (code "51") (name "Net-(RX-K)") (class "Default")
      (node (ref "R6") (pin "1") (pinfunction "1_1") (pintype "passive"))
      (node (ref "RX") (pin "2") (pinfunction "K_2") (pintype "passive"))
    )
    (net (code "52") (name "Net-(TX-A)") (class "Default")
      (node (ref "R3") (pin "2") (pinfunction "2_2") (pintype "passive"))
      (node (ref "TX") (pin "1") (pinfunction "A_1") (pintype "passive"))
    )
    (net (code "53") (name "Net-(TX-K)") (class "Default")
      (node (ref "R4") (pin "1") (pinfunction "1_1") (pintype "passive"))
      (node (ref "TX") (pin "2") (pinfunction "K_2") (pintype "passive"))
    )
    (net (code "54") (name "unconnected-(Atmega1-(CLKO{slash}ICP3{slash}INT7)_PE7-Pad9)") (class "Default")
      (node (ref "Atmega1") (pin "9") (pinfunction "(CLKO/ICP3/INT7)_PE7_9") (pintype "input"))
    )
    (net (code "55") (name "unconnected-(Atmega1-(ICP1)_PD4-Pad47)") (class "Default")
      (node (ref "Atmega1") (pin "47") (pinfunction "(ICP1)_PD4_47") (pintype "bidirectional"))
    )
    (net (code "56") (name "unconnected-(Atmega1-(ICP4)_PL0-Pad35)") (class "Default")
      (node (ref "Atmega1") (pin "35") (pinfunction "(ICP4)_PL0_35") (pintype "bidirectional"))
    )
    (net (code "57") (name "unconnected-(Atmega1-(ICP5)_PL1-Pad36)") (class "Default")
      (node (ref "Atmega1") (pin "36") (pinfunction "(ICP5)_PL1_36") (pintype "bidirectional"))
    )
    (net (code "58") (name "unconnected-(Atmega1-(OC0A{slash}OC1C{slash}PCINT7)_PB7-Pad26)") (class "Default")
      (node (ref "Atmega1") (pin "26") (pinfunction "(OC0A/OC1C/PCINT7)_PB7_26") (pintype "input"))
    )
    (net (code "59") (name "unconnected-(Atmega1-(OC1A{slash}PCINT5)_PB5-Pad24)") (class "Default")
      (node (ref "Atmega1") (pin "24") (pinfunction "(OC1A/PCINT5)_PB5_24") (pintype "input"))
    )
    (net (code "60") (name "unconnected-(Atmega1-(OC1B{slash}PCINT6)_PB6-Pad25)") (class "Default")
      (node (ref "Atmega1") (pin "25") (pinfunction "(OC1B/PCINT6)_PB6_25") (pintype "input"))
    )
    (net (code "61") (name "unconnected-(Atmega1-(OC2A{slash}PCINT4)_PB4-Pad23)") (class "Default")
      (node (ref "Atmega1") (pin "23") (pinfunction "(OC2A/PCINT4)_PB4_23") (pintype "input"))
    )
    (net (code "62") (name "unconnected-(Atmega1-(OC4A)_PH3-Pad15)") (class "Default")
      (node (ref "Atmega1") (pin "15") (pinfunction "(OC4A)_PH3_15") (pintype "bidirectional"))
    )
    (net (code "63") (name "unconnected-(Atmega1-(OC4B)_PH4-Pad16)") (class "Default")
      (node (ref "Atmega1") (pin "16") (pinfunction "(OC4B)_PH4_16") (pintype "bidirectional"))
    )
    (net (code "64") (name "unconnected-(Atmega1-(OC4C)_PH5-Pad17)") (class "Default")
      (node (ref "Atmega1") (pin "17") (pinfunction "(OC4C)_PH5_17") (pintype "bidirectional"))
    )
    (net (code "65") (name "unconnected-(Atmega1-(OC5A)_PL3-Pad38)") (class "Default")
      (node (ref "Atmega1") (pin "38") (pinfunction "(OC5A)_PL3_38") (pintype "bidirectional"))
    )
    (net (code "66") (name "unconnected-(Atmega1-(OC5B)_PL4-Pad39)") (class "Default")
      (node (ref "Atmega1") (pin "39") (pinfunction "(OC5B)_PL4_39") (pintype "bidirectional"))
    )
    (net (code "67") (name "unconnected-(Atmega1-(T0)_PD7-Pad50)") (class "Default")
      (node (ref "Atmega1") (pin "50") (pinfunction "(T0)_PD7_50") (pintype "bidirectional"))
    )
    (net (code "68") (name "unconnected-(Atmega1-(T1)_PD6-Pad49)") (class "Default")
      (node (ref "Atmega1") (pin "49") (pinfunction "(T1)_PD6_49") (pintype "bidirectional"))
    )
    (net (code "69") (name "unconnected-(Atmega1-(T3{slash}INT6)_PE6-Pad8)") (class "Default")
      (node (ref "Atmega1") (pin "8") (pinfunction "(T3/INT6)_PE6_8") (pintype "input"))
    )
    (net (code "70") (name "unconnected-(Atmega1-(T4)_PH7-Pad27)") (class "Default")
      (node (ref "Atmega1") (pin "27") (pinfunction "(T4)_PH7_27") (pintype "bidirectional"))
    )
    (net (code "71") (name "unconnected-(Atmega1-(T5)_PL2-Pad37)") (class "Default")
      (node (ref "Atmega1") (pin "37") (pinfunction "(T5)_PL2_37") (pintype "bidirectional"))
    )
    (net (code "72") (name "unconnected-(Atmega1-(TOSC1)_PG4-Pad29)") (class "Default")
      (node (ref "Atmega1") (pin "29") (pinfunction "(TOSC1)_PG4_29") (pintype "bidirectional"))
    )
    (net (code "73") (name "unconnected-(Atmega1-(TOSC2)_PG3-Pad28)") (class "Default")
      (node (ref "Atmega1") (pin "28") (pinfunction "(TOSC2)_PG3_28") (pintype "bidirectional"))
    )
    (net (code "74") (name "unconnected-(Atmega1-(XCK0{slash}AIN0)_PE2-Pad4)") (class "Default")
      (node (ref "Atmega1") (pin "4") (pinfunction "(XCK0/AIN0)_PE2_4") (pintype "input"))
    )
    (net (code "75") (name "unconnected-(Atmega1-(XCK1)_PD5-Pad48)") (class "Default")
      (node (ref "Atmega1") (pin "48") (pinfunction "(XCK1)_PD5_48") (pintype "bidirectional"))
    )
    (net (code "76") (name "unconnected-(Atmega1-(XCK2)_PH2-Pad14)") (class "Default")
      (node (ref "Atmega1") (pin "14") (pinfunction "(XCK2)_PH2_14") (pintype "bidirectional"))
    )
    (net (code "77") (name "unconnected-(Atmega1-OC5C)_PL5-Pad40)") (class "Default")
      (node (ref "Atmega1") (pin "40") (pinfunction "OC5C)_PL5_40") (pintype "bidirectional"))
    )
    (net (code "78") (name "unconnected-(Atmega1-PA0_(AD0)-Pad78)") (class "Default")
      (node (ref "Atmega1") (pin "78") (pinfunction "PA0_(AD0)_78") (pintype "bidirectional"))
    )
    (net (code "79") (name "unconnected-(Atmega1-PA1_(AD1)-Pad77)") (class "Default")
      (node (ref "Atmega1") (pin "77") (pinfunction "PA1_(AD1)_77") (pintype "bidirectional"))
    )
    (net (code "80") (name "unconnected-(Atmega1-PA2_(AD2)-Pad76)") (class "Default")
      (node (ref "Atmega1") (pin "76") (pinfunction "PA2_(AD2)_76") (pintype "bidirectional"))
    )
    (net (code "81") (name "unconnected-(Atmega1-PA3_(AD3)-Pad75)") (class "Default")
      (node (ref "Atmega1") (pin "75") (pinfunction "PA3_(AD3)_75") (pintype "bidirectional"))
    )
    (net (code "82") (name "unconnected-(Atmega1-PA4_(AD4)-Pad74)") (class "Default")
      (node (ref "Atmega1") (pin "74") (pinfunction "PA4_(AD4)_74") (pintype "bidirectional"))
    )
    (net (code "83") (name "unconnected-(Atmega1-PA5_(AD5)-Pad73)") (class "Default")
      (node (ref "Atmega1") (pin "73") (pinfunction "PA5_(AD5)_73") (pintype "bidirectional"))
    )
    (net (code "84") (name "unconnected-(Atmega1-PA6_(AD6)-Pad72)") (class "Default")
      (node (ref "Atmega1") (pin "72") (pinfunction "PA6_(AD6)_72") (pintype "bidirectional"))
    )
    (net (code "85") (name "unconnected-(Atmega1-PA7_(AD7)-Pad71)") (class "Default")
      (node (ref "Atmega1") (pin "71") (pinfunction "PA7_(AD7)_71") (pintype "bidirectional"))
    )
    (net (code "86") (name "unconnected-(Atmega1-PC0_(A8)-Pad53)") (class "Default")
      (node (ref "Atmega1") (pin "53") (pinfunction "PC0_(A8)_53") (pintype "bidirectional"))
    )
    (net (code "87") (name "unconnected-(Atmega1-PC1_(A9)-Pad54)") (class "Default")
      (node (ref "Atmega1") (pin "54") (pinfunction "PC1_(A9)_54") (pintype "bidirectional"))
    )
    (net (code "88") (name "unconnected-(Atmega1-PC2_(A10)-Pad55)") (class "Default")
      (node (ref "Atmega1") (pin "55") (pinfunction "PC2_(A10)_55") (pintype "bidirectional"))
    )
    (net (code "89") (name "unconnected-(Atmega1-PC3_(A11)-Pad56)") (class "Default")
      (node (ref "Atmega1") (pin "56") (pinfunction "PC3_(A11)_56") (pintype "bidirectional"))
    )
    (net (code "90") (name "unconnected-(Atmega1-PC4_(A12)-Pad57)") (class "Default")
      (node (ref "Atmega1") (pin "57") (pinfunction "PC4_(A12)_57") (pintype "bidirectional"))
    )
    (net (code "91") (name "unconnected-(Atmega1-PC5_(A13)-Pad58)") (class "Default")
      (node (ref "Atmega1") (pin "58") (pinfunction "PC5_(A13)_58") (pintype "bidirectional"))
    )
    (net (code "92") (name "unconnected-(Atmega1-PC6_(A14)-Pad59)") (class "Default")
      (node (ref "Atmega1") (pin "59") (pinfunction "PC6_(A14)_59") (pintype "bidirectional"))
    )
    (net (code "93") (name "unconnected-(Atmega1-PC7_(A15)-Pad60)") (class "Default")
      (node (ref "Atmega1") (pin "60") (pinfunction "PC7_(A15)_60") (pintype "bidirectional"))
    )
    (net (code "94") (name "unconnected-(Atmega1-PF3_(ADC3)-Pad94)") (class "Default")
      (node (ref "Atmega1") (pin "94") (pinfunction "PF3_(ADC3)_94") (pintype "bidirectional"))
    )
    (net (code "95") (name "unconnected-(Atmega1-PF4_(ADC4{slash}TCK)-Pad93)") (class "Default")
      (node (ref "Atmega1") (pin "93") (pinfunction "PF4_(ADC4/TCK)_93") (pintype "bidirectional"))
    )
    (net (code "96") (name "unconnected-(Atmega1-PF5_(ADC5{slash}TMS)-Pad92)") (class "Default")
      (node (ref "Atmega1") (pin "92") (pinfunction "PF5_(ADC5/TMS)_92") (pintype "bidirectional"))
    )
    (net (code "97") (name "unconnected-(Atmega1-PF6_(ADC6{slash}TDO)-Pad91)") (class "Default")
      (node (ref "Atmega1") (pin "91") (pinfunction "PF6_(ADC6/TDO)_91") (pintype "bidirectional"))
    )
    (net (code "98") (name "unconnected-(Atmega1-PF7_(ADC7{slash}TDI)-Pad90)") (class "Default")
      (node (ref "Atmega1") (pin "90") (pinfunction "PF7_(ADC7/TDI)_90") (pintype "bidirectional"))
    )
    (net (code "99") (name "unconnected-(Atmega1-PG0_(~WR)-Pad51)") (class "Default")
      (node (ref "Atmega1") (pin "51") (pinfunction "PG0_(~WR)_51") (pintype "bidirectional"))
    )
    (net (code "100") (name "unconnected-(Atmega1-PG1_(~RD)-Pad52)") (class "Default")
      (node (ref "Atmega1") (pin "52") (pinfunction "PG1_(~RD)_52") (pintype "bidirectional"))
    )
    (net (code "101") (name "unconnected-(Atmega1-PG2_(ALE)-Pad70)") (class "Default")
      (node (ref "Atmega1") (pin "70") (pinfunction "PG2_(ALE)_70") (pintype "bidirectional"))
    )
    (net (code "102") (name "unconnected-(Atmega1-PJ2_(XCK3{slash}PCINT11)-Pad65)") (class "Default")
      (node (ref "Atmega1") (pin "65") (pinfunction "PJ2_(XCK3/PCINT11)_65") (pintype "input"))
    )
    (net (code "103") (name "unconnected-(Atmega1-PJ3_(PCINT12)-Pad66)") (class "Default")
      (node (ref "Atmega1") (pin "66") (pinfunction "PJ3_(PCINT12)_66") (pintype "input"))
    )
    (net (code "104") (name "unconnected-(Atmega1-PJ4_(PCINT13)-Pad67)") (class "Default")
      (node (ref "Atmega1") (pin "67") (pinfunction "PJ4_(PCINT13)_67") (pintype "input"))
    )
    (net (code "105") (name "unconnected-(Atmega1-PJ5_(PCINT14)-Pad68)") (class "Default")
      (node (ref "Atmega1") (pin "68") (pinfunction "PJ5_(PCINT14)_68") (pintype "input"))
    )
    (net (code "106") (name "unconnected-(Atmega1-PJ6_(PCINT15)-Pad69)") (class "Default")
      (node (ref "Atmega1") (pin "69") (pinfunction "PJ6_(PCINT15)_69") (pintype "input"))
    )
    (net (code "107") (name "unconnected-(Atmega1-PJ7-Pad79)") (class "Default")
      (node (ref "Atmega1") (pin "79") (pinfunction "PJ7_79") (pintype "bidirectional"))
    )
    (net (code "108") (name "unconnected-(Atmega1-PK0_(ADC8{slash}PCINT16)-Pad89)") (class "Default")
      (node (ref "Atmega1") (pin "89") (pinfunction "PK0_(ADC8/PCINT16)_89") (pintype "input"))
    )
    (net (code "109") (name "unconnected-(Atmega1-PK1_(ADC9{slash}PCINT17)-Pad88)") (class "Default")
      (node (ref "Atmega1") (pin "88") (pinfunction "PK1_(ADC9/PCINT17)_88") (pintype "input"))
    )
    (net (code "110") (name "unconnected-(Atmega1-PK2_(ADC10{slash}PCINT18)-Pad87)") (class "Default")
      (node (ref "Atmega1") (pin "87") (pinfunction "PK2_(ADC10/PCINT18)_87") (pintype "input"))
    )
    (net (code "111") (name "unconnected-(Atmega1-PK3_(ADC11{slash}PCINT19)-Pad86)") (class "Default")
      (node (ref "Atmega1") (pin "86") (pinfunction "PK3_(ADC11/PCINT19)_86") (pintype "input"))
    )
    (net (code "112") (name "unconnected-(Atmega1-PK4_(ADC12{slash}PCINT20)-Pad85)") (class "Default")
      (node (ref "Atmega1") (pin "85") (pinfunction "PK4_(ADC12/PCINT20)_85") (pintype "input"))
    )
    (net (code "113") (name "unconnected-(Atmega1-PK5_(ADC13{slash}PCINT21)-Pad84)") (class "Default")
      (node (ref "Atmega1") (pin "84") (pinfunction "PK5_(ADC13/PCINT21)_84") (pintype "input"))
    )
    (net (code "114") (name "unconnected-(Atmega1-PK6_(ADC14{slash}PCINT22)-Pad83)") (class "Default")
      (node (ref "Atmega1") (pin "83") (pinfunction "PK6_(ADC14/PCINT22)_83") (pintype "input"))
    )
    (net (code "115") (name "unconnected-(Atmega1-PK7_(ADC15{slash}PCINT23)-Pad82)") (class "Default")
      (node (ref "Atmega1") (pin "82") (pinfunction "PK7_(ADC15/PCINT23)_82") (pintype "input"))
    )
    (net (code "116") (name "unconnected-(Atmega1-PL6-Pad41)") (class "Default")
      (node (ref "Atmega1") (pin "41") (pinfunction "PL6_41") (pintype "bidirectional"))
    )
    (net (code "117") (name "unconnected-(Atmega1-PL7-Pad42)") (class "Default")
      (node (ref "Atmega1") (pin "42") (pinfunction "PL7_42") (pintype "bidirectional"))
    )
    (net (code "118") (name "unconnected-(J1-Pad1)") (class "Default")
      (node (ref "J1") (pin "1") (pinfunction "1_1") (pintype "bidirectional"))
    )
    (net (code "119") (name "unconnected-(J1-Pad2)") (class "Default")
      (node (ref "J1") (pin "2") (pinfunction "2_2") (pintype "bidirectional"))
    )
    (net (code "120") (name "unconnected-(J1-Pad3)") (class "Default")
      (node (ref "J1") (pin "3") (pinfunction "3_3") (pintype "bidirectional"))
    )
    (net (code "121") (name "unconnected-(J1-Pad4)") (class "Default")
      (node (ref "J1") (pin "4") (pinfunction "4_4") (pintype "bidirectional"))
    )
    (net (code "122") (name "unconnected-(J1-Pad5)") (class "Default")
      (node (ref "J1") (pin "5") (pinfunction "5_5") (pintype "bidirectional"))
    )
    (net (code "123") (name "unconnected-(J1-Pad6)") (class "Default")
      (node (ref "J1") (pin "6") (pinfunction "6_6") (pintype "bidirectional"))
    )
    (net (code "124") (name "unconnected-(J1-Pad7)") (class "Default")
      (node (ref "J1") (pin "7") (pinfunction "7_7") (pintype "bidirectional"))
    )
    (net (code "125") (name "unconnected-(J1-Pad8)") (class "Default")
      (node (ref "J1") (pin "8") (pinfunction "8_8") (pintype "bidirectional"))
    )
    (net (code "126") (name "unconnected-(J1-Pad18)") (class "Default")
      (node (ref "J1") (pin "18") (pinfunction "18_18") (pintype "bidirectional"))
    )
    (net (code "127") (name "unconnected-(J2-Pad2)") (class "Default")
      (node (ref "J2") (pin "2") (pinfunction "2_2") (pintype "bidirectional"))
    )
    (net (code "128") (name "unconnected-(J2-Pad3)") (class "Default")
      (node (ref "J2") (pin "3") (pinfunction "3_3") (pintype "bidirectional"))
    )
    (net (code "129") (name "unconnected-(J2-Pad4)") (class "Default")
      (node (ref "J2") (pin "4") (pinfunction "4_4") (pintype "bidirectional"))
    )
    (net (code "130") (name "unconnected-(J2-Pad5)") (class "Default")
      (node (ref "J2") (pin "5") (pinfunction "5_5") (pintype "bidirectional"))
    )
    (net (code "131") (name "unconnected-(J2-Pad7)") (class "Default")
      (node (ref "J2") (pin "7") (pinfunction "7_7") (pintype "bidirectional"))
    )
    (net (code "132") (name "unconnected-(J2-Pad9)") (class "Default")
      (node (ref "J2") (pin "9") (pinfunction "9_9") (pintype "bidirectional"))
    )
    (net (code "133") (name "unconnected-(J2-Pad12)") (class "Default")
      (node (ref "J2") (pin "12") (pinfunction "12_12") (pintype "bidirectional"))
    )
    (net (code "134") (name "unconnected-(J2-Pad13)") (class "Default")
      (node (ref "J2") (pin "13") (pinfunction "13_13") (pintype "bidirectional"))
    )
    (net (code "135") (name "unconnected-(J2-Pad14)") (class "Default")
      (node (ref "J2") (pin "14") (pinfunction "14_14") (pintype "bidirectional"))
    )
    (net (code "136") (name "unconnected-(J2-Pad15)") (class "Default")
      (node (ref "J2") (pin "15") (pinfunction "15_15") (pintype "bidirectional"))
    )
    (net (code "137") (name "unconnected-(MPU9250-AD0{slash}SDO-Pad9)") (class "Default")
      (node (ref "MPU9250") (pin "9") (pinfunction "AD0/SDO_9") (pintype "output"))
    )
    (net (code "138") (name "unconnected-(MPU9250-AUX_CL-Pad7)") (class "Default")
      (node (ref "MPU9250") (pin "7") (pinfunction "AUX_CL_7") (pintype "input"))
    )
    (net (code "139") (name "unconnected-(MPU9250-AUX_DA-Pad21)") (class "Default")
      (node (ref "MPU9250") (pin "21") (pinfunction "AUX_DA_21") (pintype "input"))
    )
    (net (code "140") (name "unconnected-(MPU9250-EXP-Pad25)") (class "Default")
      (node (ref "MPU9250") (pin "25") (pinfunction "EXP_25") (pintype "passive"))
    )
    (net (code "141") (name "unconnected-(MPU9250-FSYNC-Pad11)") (class "Default")
      (node (ref "MPU9250") (pin "11") (pinfunction "FSYNC_11") (pintype "input"))
    )
    (net (code "142") (name "unconnected-(MPU9250-INT-Pad12)") (class "Default")
      (node (ref "MPU9250") (pin "12") (pinfunction "INT_12") (pintype "output"))
    )
    (net (code "143") (name "unconnected-(MPU9250-NC-Pad2)") (class "Default")
      (node (ref "MPU9250") (pin "2") (pinfunction "NC_2") (pintype "passive"))
    )
    (net (code "144") (name "unconnected-(MPU9250-NC-Pad3)") (class "Default")
      (node (ref "MPU9250") (pin "3") (pinfunction "NC_3") (pintype "passive"))
    )
    (net (code "145") (name "unconnected-(MPU9250-NC-Pad4)") (class "Default")
      (node (ref "MPU9250") (pin "4") (pinfunction "NC_4") (pintype "passive"))
    )
    (net (code "146") (name "unconnected-(MPU9250-NC-Pad5)") (class "Default")
      (node (ref "MPU9250") (pin "5") (pinfunction "NC_5") (pintype "passive"))
    )
    (net (code "147") (name "unconnected-(MPU9250-NC-Pad6)") (class "Default")
      (node (ref "MPU9250") (pin "6") (pinfunction "NC_6") (pintype "passive"))
    )
    (net (code "148") (name "unconnected-(MPU9250-NC-Pad14)") (class "Default")
      (node (ref "MPU9250") (pin "14") (pinfunction "NC_14") (pintype "passive"))
    )
    (net (code "149") (name "unconnected-(MPU9250-NC-Pad15)") (class "Default")
      (node (ref "MPU9250") (pin "15") (pinfunction "NC_15") (pintype "passive"))
    )
    (net (code "150") (name "unconnected-(MPU9250-NC-Pad16)") (class "Default")
      (node (ref "MPU9250") (pin "16") (pinfunction "NC_16") (pintype "passive"))
    )
    (net (code "151") (name "unconnected-(MPU9250-NC-Pad17)") (class "Default")
      (node (ref "MPU9250") (pin "17") (pinfunction "NC_17") (pintype "passive"))
    )
    (net (code "152") (name "unconnected-(MPU9250-RESV_19-Pad19)") (class "Default")
      (node (ref "MPU9250") (pin "19") (pinfunction "RESV_19_19") (pintype "passive"))
    )
    (net (code "153") (name "unconnected-(MPU9250-~{CS}-Pad22)") (class "Default")
      (node (ref "MPU9250") (pin "22") (pinfunction "~{CS}_22") (pintype "input"))
    )
  )
)
